# CAN.net
KiCad netlist of a schematic drawn in Altium Designer
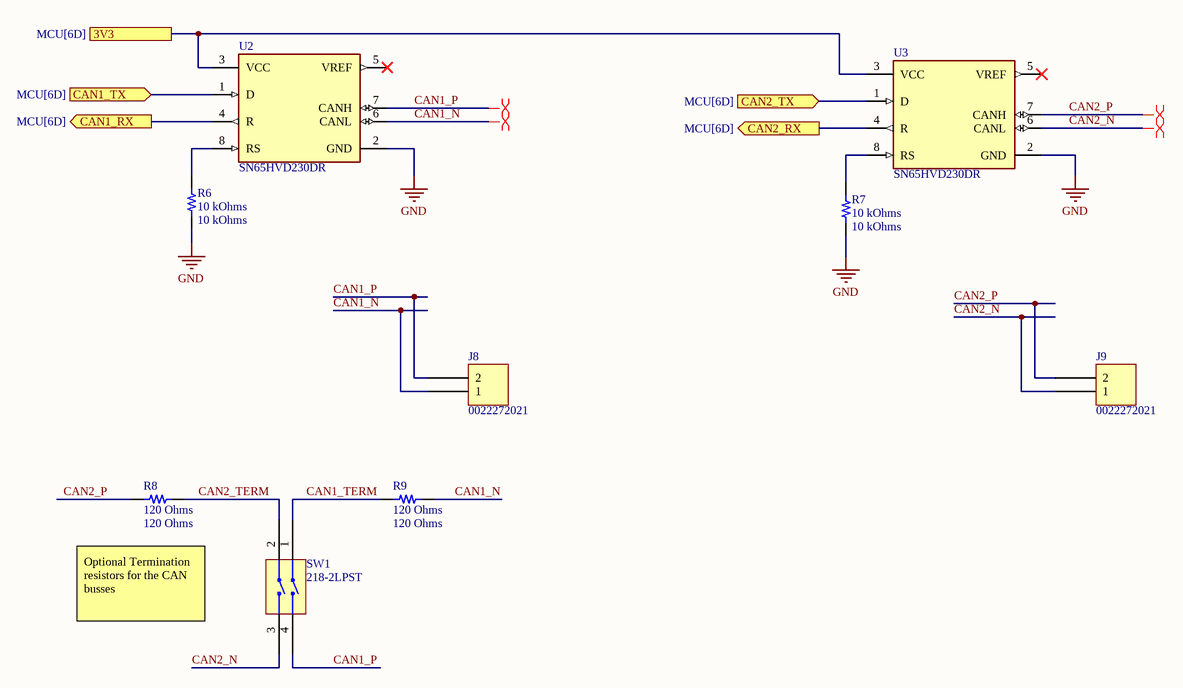
[diagram p0: CAN.SchDoc]

(export (version "E")
  (design (tool "Eeschema 10.0.6"))
  (components
    (comp (ref "J8")
      (value "0022272021")
      (footprint "MOLEX KK 0022272021")
      (description "CONN HEADER VERT 2POS 2.54MM")
      (libsource (lib "altium_library") (part "2 Pin"))
    )
    (comp (ref "J9")
      (value "0022272021")
      (footprint "MOLEX KK 0022272021")
      (description "CONN HEADER VERT 2POS 2.54MM")
      (libsource (lib "altium_library") (part "2 Pin"))
    )
    (comp (ref "R6")
      (value "10 kOhms")
      (footprint "RES 0603_1608")
      (description "RES SMD 10K OHM 1% 1/10W 0603")
      (fields (field (name "PART NUMBER") "AA0603FR-0710KL") (field (name "ALTIUM_VALUE") "10 kOhms"))
      (libsource (lib "altium_library") (part "Resistor"))
    )
    (comp (ref "R7")
      (value "10 kOhms")
      (footprint "RES 0603_1608")
      (description "RES SMD 10K OHM 1% 1/10W 0603")
      (fields (field (name "PART NUMBER") "AA0603FR-0710KL") (field (name "ALTIUM_VALUE") "10 kOhms"))
      (libsource (lib "altium_library") (part "Resistor"))
    )
    (comp (ref "R8")
      (value "120 Ohms")
      (footprint "RES 0603_1608")
      (description "RES SMD 120 OHM 0.1% 1/10W 0603")
      (fields (field (name "PART NUMBER") "ERA-3AEB121V") (field (name "ALTIUM_VALUE") "120 Ohms"))
      (libsource (lib "altium_library") (part "Resistor"))
    )
    (comp (ref "R9")
      (value "120 Ohms")
      (footprint "RES 0603_1608")
      (description "RES SMD 120 OHM 0.1% 1/10W 0603")
      (fields (field (name "PART NUMBER") "ERA-3AEB121V") (field (name "ALTIUM_VALUE") "120 Ohms"))
      (libsource (lib "altium_library") (part "Resistor"))
    )
    (comp (ref "SW1")
      (value "218-2LPST")
      (footprint "CTS 218-2LPJ")
      (description "SWITCH SLIDE DIP SPST 25MA 24V")
      (libsource (lib "altium_library") (part "DIP SW 2P"))
    )
    (comp (ref "U2")
      (value "SN65HVD230DR")
      (footprint "FP-D0008A-IPC_A")
      (description "IC TRANSCEIVER HALF 1/1 8SOIC")
      (libsource (lib "Altium Content Vault") (part "43b56812b1adf0e60a7acfb7c27ab91"))
    )
    (comp (ref "U3")
      (value "SN65HVD230DR")
      (footprint "FP-D0008A-IPC_A")
      (description "IC TRANSCEIVER HALF 1/1 8SOIC")
      (libsource (lib "Altium Content Vault") (part "43b56812b1adf0e60a7acfb7c27ab91"))
    )
  )
  (nets
    (net (code "1") (name "/3V3") (class "Default")
      (node (ref "U2") (pin "3") (pinfunction "VCC_3") (pintype "power_in"))
      (node (ref "U3") (pin "3") (pinfunction "VCC_3") (pintype "power_in"))
    )
    (net (code "2") (name "/CAN1_N") (class "Default")
      (node (ref "J8") (pin "1") (pinfunction "1_1") (pintype "passive"))
      (node (ref "R9") (pin "2") (pinfunction "2_2") (pintype "passive"))
      (node (ref "U2") (pin "6") (pinfunction "CANL_6") (pintype "bidirectional"))
    )
    (net (code "3") (name "/CAN1_P") (class "Default")
      (node (ref "J8") (pin "2") (pinfunction "2_2") (pintype "passive"))
      (node (ref "SW1") (pin "4") (pinfunction "GND_4") (pintype "passive"))
      (node (ref "U2") (pin "7") (pinfunction "CANH_7") (pintype "bidirectional"))
    )
    (net (code "4") (name "/CAN1_RX") (class "Default")
      (node (ref "U2") (pin "4") (pinfunction "R_4") (pintype "output"))
    )
    (net (code "5") (name "/CAN1_TERM") (class "Default")
      (node (ref "R9") (pin "1") (pinfunction "1_1") (pintype "passive"))
      (node (ref "SW1") (pin "1") (pinfunction "GND_1") (pintype "passive"))
    )
    (net (code "6") (name "/CAN1_TX") (class "Default")
      (node (ref "U2") (pin "1") (pinfunction "D_1") (pintype "input"))
    )
    (net (code "7") (name "/CAN2_N") (class "Default")
      (node (ref "J9") (pin "1") (pinfunction "1_1") (pintype "passive"))
      (node (ref "SW1") (pin "3") (pinfunction "GND_3") (pintype "passive"))
      (node (ref "U3") (pin "6") (pinfunction "CANL_6") (pintype "bidirectional"))
    )
    (net (code "8") (name "/CAN2_P") (class "Default")
      (node (ref "J9") (pin "2") (pinfunction "2_2") (pintype "passive"))
      (node (ref "R8") (pin "1") (pinfunction "1_1") (pintype "passive"))
      (node (ref "U3") (pin "7") (pinfunction "CANH_7") (pintype "bidirectional"))
    )
    (net (code "9") (name "/CAN2_RX") (class "Default")
      (node (ref "U3") (pin "4") (pinfunction "R_4") (pintype "output"))
    )
    (net (code "10") (name "/CAN2_TERM") (class "Default")
      (node (ref "R8") (pin "2") (pinfunction "2_2") (pintype "passive"))
      (node (ref "SW1") (pin "2") (pinfunction "GND_2") (pintype "passive"))
    )
    (net (code "11") (name "/CAN2_TX") (class "Default")
      (node (ref "U3") (pin "1") (pinfunction "D_1") (pintype "input"))
    )
    (net (code "12") (name "GND") (class "Default")
      (node (ref "R6") (pin "1") (pinfunction "1_1") (pintype "passive"))
      (node (ref "R7") (pin "1") (pinfunction "1_1") (pintype "passive"))
      (node (ref "U2") (pin "2") (pinfunction "GND_2") (pintype "power_in"))
      (node (ref "U3") (pin "2") (pinfunction "GND_2") (pintype "power_in"))
    )
    (net (code "13") (name "Net-(U2-RS)") (class "Default")
      (node (ref "R6") (pin "2") (pinfunction "2_2") (pintype "passive"))
      (node (ref "U2") (pin "8") (pinfunction "RS_8") (pintype "input"))
    )
    (net (code "14") (name "Net-(U3-RS)") (class "Default")
      (node (ref "R7") (pin "2") (pinfunction "2_2") (pintype "passive"))
      (node (ref "U3") (pin "8") (pinfunction "RS_8") (pintype "input"))
    )
    (net (code "15") (name "unconnected-(U2-VREF-Pad5)") (class "Default")
      (node (ref "U2") (pin "5") (pinfunction "VREF_5") (pintype "output+no_connect"))
    )
    (net (code "16") (name "unconnected-(U3-VREF-Pad5)") (class "Default")
      (node (ref "U3") (pin "5") (pinfunction "VREF_5") (pintype "output+no_connect"))
    )
  )
)
